# Schmeatic.net
KiCad netlist of a schematic drawn in Altium Designer
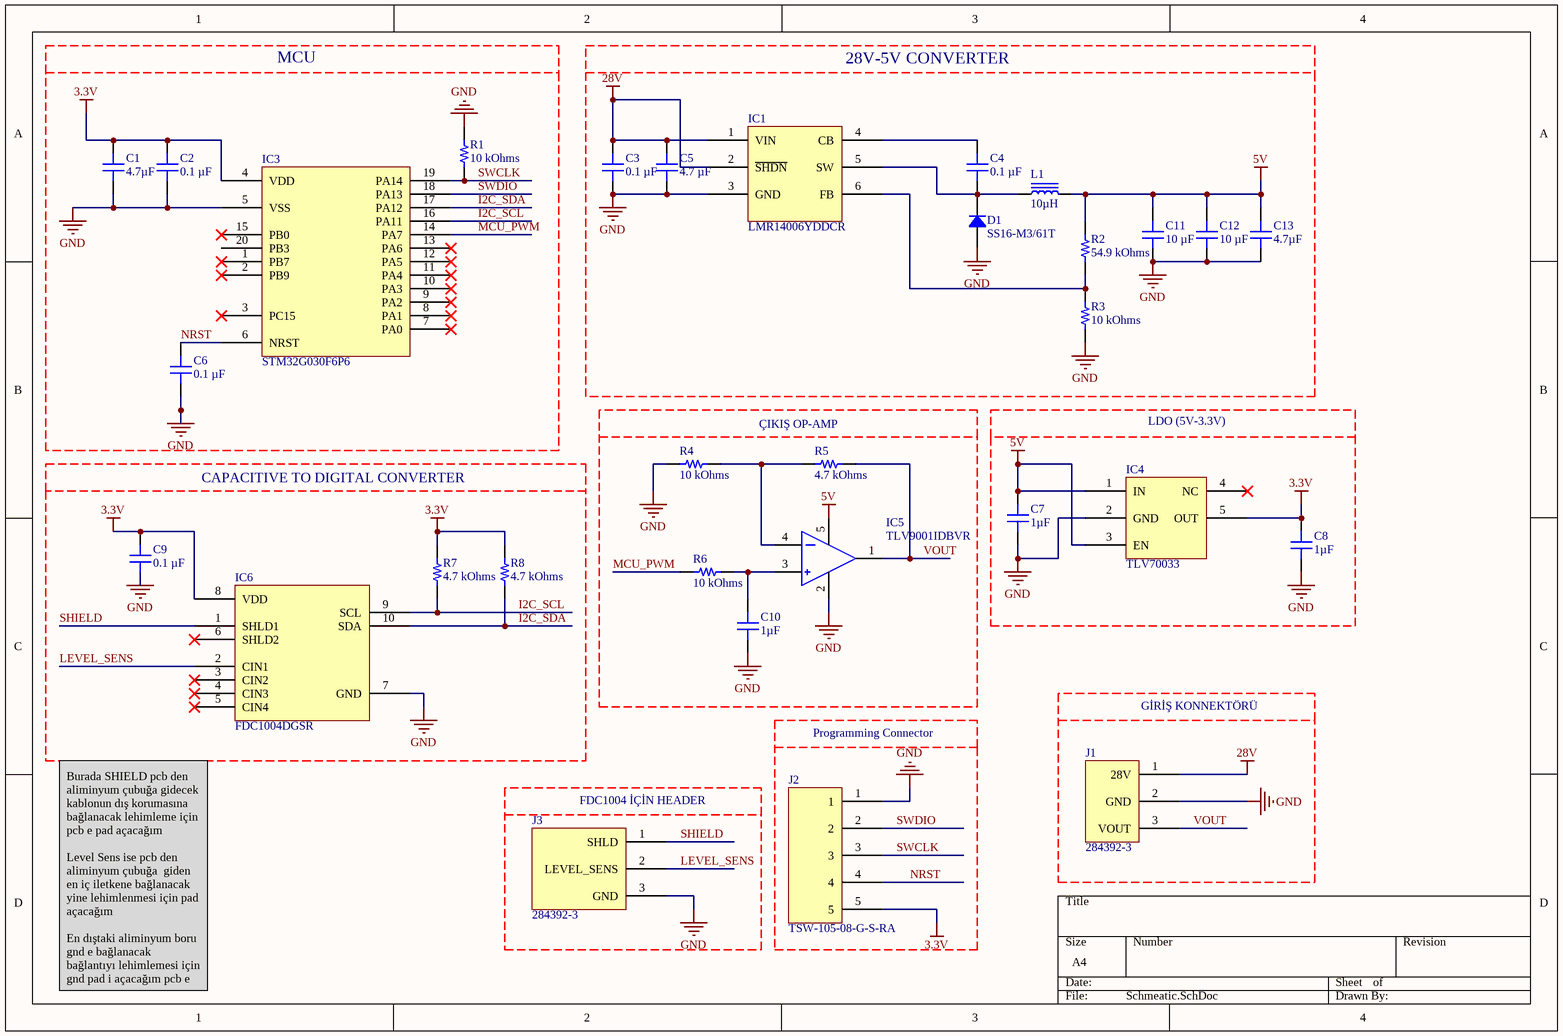
[diagram p0: Schmeatic.SchDoc]

(export (version "E")
  (design (tool "Eeschema 10.0.6"))
  (components
    (comp (ref "C1")
      (value "4.7µF")
      (footprint "CAP 0805_2012")
      (description "CAP CER 4.7UF 16V X7R 0805")
      (fields
        (field (name "PART NUMBER") "0805YC475MAT2A")
        (field (name "CAPACITANCE") "4.7µF")
        (field (name "MANUFACTURER") "AVX Corporation")
      )
      (libsource (lib "Celestial Altium Library - altium_library") (part "Capacitor"))
    )
    (comp (ref "C2")
      (value "0.1 µF")
      (footprint "CAP 0805_2012")
      (description "CAP CER 0.1UF 16V X7R 0805")
      (fields
        (field (name "PART NUMBER") "160R15W104KV4T")
        (field (name "CAPACITANCE") "0.1 µF")
        (field (name "MANUFACTURER") "Johanson Dielectrics Inc.")
      )
      (libsource (lib "Celestial Altium Library - altium_library") (part "Capacitor"))
    )
    (comp (ref "C3")
      (value "0.1 µF")
      (footprint "CAP 0805_2012")
      (description "CAP CER 0.1UF 50V X7R 0805")
      (fields
        (field (name "PART NUMBER") "885012207098")
        (field (name "CAPACITANCE") "0.1 µF")
        (field (name "MANUFACTURER") "Würth Elektronik")
      )
      (libsource (lib "Celestial Altium Library - altium_library") (part "Capacitor"))
    )
    (comp (ref "C4")
      (value "0.1 µF")
      (footprint "CAP 0805_2012")
      (description "CAP CER 0.1UF 25V X7R 0805")
      (fields
        (field (name "PART NUMBER") "0805Y0250104KXT")
        (field (name "CAPACITANCE") "0.1 µF")
        (field (name "MANUFACTURER") "Knowles Syfer")
      )
      (libsource (lib "Celestial Altium Library - altium_library") (part "Capacitor"))
    )
    (comp (ref "C5")
      (value "4.7 µF")
      (footprint "CAP 0805_2012")
      (description "CAP CER 4.7UF 50V X7R 0805")
      (fields
        (field (name "PART NUMBER") "CGA4J1X7R1H475K125AE")
        (field (name "CAPACITANCE") "4.7 µF")
        (field (name "MANUFACTURER") "TDK Corporation")
      )
      (libsource (lib "Celestial Altium Library - altium_library") (part "Capacitor"))
    )
    (comp (ref "C6")
      (value "0.1 µF")
      (footprint "CAP 0805_2012")
      (description "CAP CER 0.1UF 16V X7R 0805")
      (fields
        (field (name "PART NUMBER") "160R15W104KV4T")
        (field (name "CAPACITANCE") "0.1 µF")
        (field (name "MANUFACTURER") "Johanson Dielectrics Inc.")
      )
      (libsource (lib "Celestial Altium Library - altium_library") (part "Capacitor"))
    )
    (comp (ref "C7")
      (value "1µF")
      (footprint "CAP 0805_2012")
      (description "CAP CER 1UF 16V X7R 0805")
      (fields
        (field (name "PART NUMBER") "0805YC105KAT4A")
        (field (name "CAPACITANCE") "1µF")
        (field (name "MANUFACTURER") "AVX Corporation")
      )
      (libsource (lib "Celestial Altium Library - altium_library") (part "Capacitor"))
    )
    (comp (ref "C8")
      (value "1µF")
      (footprint "CAP 0805_2012")
      (description "CAP CER 1UF 16V X7R 0805")
      (fields
        (field (name "PART NUMBER") "0805YC105KAT4A")
        (field (name "CAPACITANCE") "1µF")
        (field (name "MANUFACTURER") "AVX Corporation")
      )
      (libsource (lib "Celestial Altium Library - altium_library") (part "Capacitor"))
    )
    (comp (ref "C9")
      (value "0.1 µF")
      (footprint "CAP 0805_2012")
      (description "CAP CER 0.1UF 16V X7R 0805")
      (fields
        (field (name "PART NUMBER") "160R15W104KV4T")
        (field (name "CAPACITANCE") "0.1 µF")
        (field (name "MANUFACTURER") "Johanson Dielectrics Inc.")
      )
      (libsource (lib "Celestial Altium Library - altium_library") (part "Capacitor"))
    )
    (comp (ref "C10")
      (value "1µF")
      (footprint "CAP 0805_2012")
      (description "CAP CER 1UF 16V X7R 0805")
      (fields
        (field (name "PART NUMBER") "0805YC105KAT4A")
        (field (name "CAPACITANCE") "1µF")
        (field (name "MANUFACTURER") "AVX Corporation")
      )
      (libsource (lib "Celestial Altium Library - altium_library") (part "Capacitor"))
    )
    (comp (ref "C11")
      (value "10 µF")
      (footprint "MURATA GRM21B 0805_2012")
      (description "CAP CER 10UF 25V X7R 0805")
      (fields
        (field (name "PART NUMBER") "GRM21BZ71E106KE15L")
        (field (name "CAPACITANCE") "10 µF")
        (field (name "MANUFACTURER") "Murata Electronics")
      )
      (libsource (lib "Celestial Altium Library - altium_library") (part "Capacitor"))
    )
    (comp (ref "C12")
      (value "10 µF")
      (footprint "MURATA GRM21B 0805_2012")
      (description "CAP CER 10UF 25V X7R 0805")
      (fields
        (field (name "PART NUMBER") "GRM21BZ71E106KE15L")
        (field (name "CAPACITANCE") "10 µF")
        (field (name "MANUFACTURER") "Murata Electronics")
      )
      (libsource (lib "Celestial Altium Library - altium_library") (part "Capacitor"))
    )
    (comp (ref "C13")
      (value "4.7µF")
      (footprint "CAP 0805_2012")
      (description "CAP CER 4.7UF 25V X7R 0805")
      (fields
        (field (name "PART NUMBER") "08053C475MAT2A")
        (field (name "CAPACITANCE") "4.7µF")
        (field (name "MANUFACTURER") "AVX Corporation")
      )
      (libsource (lib "Celestial Altium Library - altium_library") (part "Capacitor"))
    )
    (comp (ref "D1")
      (value "SS16-M3/61T")
      (footprint "DO214AC SMA")
      (description "DIODE SCHOTTKY 1A 60V DO-214AC")
      (fields (field (name "MANUFACTURER") "Vishay Semiconductor Diodes Division"))
      (libsource (lib "Celestial Altium Library - altium_library") (part "Diode"))
    )
    (comp (ref "IC1")
      (value "LMR14006YDDCR")
      (footprint "PcbLib1:TSOT-23-6")
      (description "Buck Switching Regulator IC Positive Adjustable 0.765V 1 Output 600mA SOT-23-6 Thin, TSOT-23-6")
      (libsource (lib "Schlib1") (part "LMR14006YDDCR"))
    )
    (comp (ref "IC3")
      (value "STM32G030F6P6")
      (footprint "TSSOP20")
      (description "ARM® Cortex®-M0+ STM32G0 Microcontroller IC 32-Bit 64MHz 32KB (32K x 8) FLASH 20-TSSOP")
      (libsource (lib "Schlib1") (part "STM32G030F6P6"))
    )
    (comp (ref "IC4")
      (value "TLV70033")
      (footprint "SOT23-5")
      (description "Linear Voltage Regulator IC Positive Fixed 1 Output 200mA SC-70-5")
      (libsource (lib "Schlib1") (part "TLV70033"))
    )
    (comp (ref "IC5")
      (value "TLV9001IDBVR")
      (footprint "PcbLib1:SOT23-5")
      (description "CMOS Amplifier 1 Circuit Rail-to-Rail SOT-23-5")
      (libsource (lib "Schlib1") (part "TLV9001IDBVR"))
    )
    (comp (ref "IC6")
      (value "FDC1004DGSR")
      (footprint "10-VSSOP (DGS)")
      (description "Capacitive Touch Proximity Only 10-VSSOP")
      (libsource (lib "Schlib1") (part "FDC1004DGSR"))
    )
    (comp (ref "J1")
      (value "284392-3")
      (footprint "PcbLib1:284392-3")
      (description "3 Position Wire to Board Terminal Block Horizontal with Board 0.150\" (3.81mm) Through Hole")
      (libsource (lib "Schlib1") (part "284392-3"))
    )
    (comp (ref "J2")
      (value "TSW-105-08-G-S-RA")
      (footprint "TSW-105-08-G-S-RA")
      (description "Connector Header Through Hole, Right Angle 5 position 0.100\" (2.54mm)")
      (libsource (lib "Schlib1") (part "TSW-105-08-G-S-RA"))
    )
    (comp (ref "J3")
      (value "284392-3")
      (footprint "284392-3")
      (description "3 Position Wire to Board Terminal Block Horizontal with Board 0.150\" (3.81mm) Through Hole")
      (libsource (lib "Schlib1") (part "284392-3 (FDC1004 İÇİN)"))
    )
    (comp (ref "L1")
      (value "10µH")
      (footprint "TDK SLF7032")
      (description "FIXED IND 10UH 1.4A 63.6 MOHM")
      (fields
        (field (name "PART NUMBER") "SLF7032T-100M1R4-2PF")
        (field (name "MANUFACTURER") "TDK Corporation")
      )
      (libsource (lib "Celestial Altium Library - altium_library") (part "Inductor"))
    )
    (comp (ref "R1")
      (value "10 kOhms")
      (footprint "YAGEO RES 0805_2012")
      (description "RES 10K OHM 1% 1/8W 0805")
      (fields (field (name "PART NUMBER") "RV0805FR-0710KL") (field (name "MANUFACTURER") "Yageo"))
      (libsource (lib "Celestial Altium Library - altium_library") (part "Resistor"))
    )
    (comp (ref "R2")
      (value "54.9 kOhms")
      (footprint "RES 0805_2012")
      (description "RES SMD 54.9K OHM 1% 1/8W 0805")
      (fields (field (name "PART NUMBER") "CRCW080554K9FKEA") (field (name "MANUFACTURER") "Vishay Dale"))
      (libsource (lib "Celestial Altium Library - altium_library") (part "Resistor"))
    )
    (comp (ref "R3")
      (value "10 kOhms")
      (footprint "YAGEO RES 0805_2012")
      (description "RES SMD 10K OHM 1% 1/8W 0805")
      (fields (field (name "PART NUMBER") "RT0805FRE0710KL") (field (name "MANUFACTURER") "Yageo"))
      (libsource (lib "Celestial Altium Library - altium_library") (part "Resistor"))
    )
    (comp (ref "R4")
      (value "10 kOhms")
      (footprint "RES 0805_2012")
      (description "RES SMD 10K OHM 1% 1/8W 0805")
      (fields (field (name "PART NUMBER") "CRCW080510K0FKEA") (field (name "MANUFACTURER") "Vishay Dale"))
      (libsource (lib "Celestial Altium Library - altium_library") (part "Resistor"))
    )
    (comp (ref "R5")
      (value "4.7 kOhms")
      (footprint "YAGEO RES 0805_2012")
      (description "RES 4.7K OHM 1% 1/8W 0805")
      (fields (field (name "PART NUMBER") "RC0805FR-074K7P") (field (name "MANUFACTURER") "Yageo"))
      (libsource (lib "Celestial Altium Library - altium_library") (part "Resistor"))
    )
    (comp (ref "R6")
      (value "10 kOhms")
      (footprint "RES 0805_2012")
      (description "RES SMD 10K OHM 1% 1/8W 0805")
      (fields (field (name "PART NUMBER") "CRCW080510K0FKEA") (field (name "MANUFACTURER") "Vishay Dale"))
      (libsource (lib "Celestial Altium Library - altium_library") (part "Resistor"))
    )
    (comp (ref "R7")
      (value "4.7 kOhms")
      (footprint "YAGEO RES 0805_2012")
      (description "RES 4.7K OHM 1% 1/8W 0805")
      (fields (field (name "PART NUMBER") "RC0805FR-074K7P") (field (name "MANUFACTURER") "Yageo"))
      (libsource (lib "Celestial Altium Library - altium_library") (part "Resistor"))
    )
    (comp (ref "R8")
      (value "4.7 kOhms")
      (footprint "YAGEO RES 0805_2012")
      (description "RES 4.7K OHM 1% 1/8W 0805")
      (fields (field (name "PART NUMBER") "RC0805FR-074K7P") (field (name "MANUFACTURER") "Yageo"))
      (libsource (lib "Celestial Altium Library - altium_library") (part "Resistor"))
    )
  )
  (nets
    (net (code "1") (name "/I2C_SCL") (class "Default")
      (node (ref "IC3") (pin "16") (pinfunction "PA11_16") (pintype "passive"))
      (node (ref "IC6") (pin "9") (pinfunction "SCL_9") (pintype "passive"))
      (node (ref "R7") (pin "1") (pinfunction "1_1") (pintype "passive"))
    )
    (net (code "2") (name "/I2C_SDA") (class "Default")
      (node (ref "IC3") (pin "17") (pinfunction "PA12_17") (pintype "passive"))
      (node (ref "IC6") (pin "10") (pinfunction "SDA_10") (pintype "passive"))
      (node (ref "R8") (pin "1") (pinfunction "1_1") (pintype "passive"))
    )
    (net (code "3") (name "/LEVEL_SENS") (class "Default")
      (node (ref "IC6") (pin "2") (pinfunction "CIN1_2") (pintype "passive"))
      (node (ref "J3") (pin "2") (pinfunction "LEVEL_SENS_2") (pintype "passive"))
    )
    (net (code "4") (name "/MCU_PWM") (class "Default")
      (node (ref "IC3") (pin "14") (pinfunction "PA7_14") (pintype "passive"))
      (node (ref "R6") (pin "1") (pinfunction "1_1") (pintype "passive"))
    )
    (net (code "5") (name "/NRST") (class "Default")
      (node (ref "C6") (pin "2") (pinfunction "2_2") (pintype "passive"))
      (node (ref "IC3") (pin "6") (pinfunction "NRST_6") (pintype "passive"))
      (node (ref "J2") (pin "4") (pinfunction "4_4") (pintype "passive"))
    )
    (net (code "6") (name "/SHIELD") (class "Default")
      (node (ref "IC6") (pin "1") (pinfunction "SHLD1_1") (pintype "passive"))
      (node (ref "J3") (pin "1") (pinfunction "SHLD_1") (pintype "passive"))
    )
    (net (code "7") (name "/SWCLK") (class "Default")
      (node (ref "IC3") (pin "19") (pinfunction "PA14_19") (pintype "passive"))
      (node (ref "J2") (pin "3") (pinfunction "3_3") (pintype "passive"))
      (node (ref "R1") (pin "1") (pinfunction "1_1") (pintype "passive"))
    )
    (net (code "8") (name "/SWDIO") (class "Default")
      (node (ref "IC3") (pin "18") (pinfunction "PA13_18") (pintype "passive"))
      (node (ref "J2") (pin "2") (pinfunction "2_2") (pintype "passive"))
    )
    (net (code "9") (name "/VOUT") (class "Default")
      (node (ref "IC5") (pin "1") (pinfunction "1_1") (pintype "passive"))
      (node (ref "J1") (pin "3") (pinfunction "VOUT_3") (pintype "passive"))
      (node (ref "R5") (pin "2") (pinfunction "2_2") (pintype "passive"))
    )
    (net (code "10") (name "3.3V") (class "Default")
      (node (ref "C1") (pin "2") (pinfunction "2_2") (pintype "passive"))
      (node (ref "C2") (pin "2") (pinfunction "2_2") (pintype "passive"))
      (node (ref "C8") (pin "1") (pinfunction "1_1") (pintype "passive"))
      (node (ref "C9") (pin "2") (pinfunction "2_2") (pintype "passive"))
      (node (ref "IC3") (pin "4") (pinfunction "VDD_4") (pintype "passive"))
      (node (ref "IC4") (pin "5") (pinfunction "OUT_5") (pintype "passive"))
      (node (ref "IC6") (pin "8") (pinfunction "VDD_8") (pintype "passive"))
      (node (ref "J2") (pin "5") (pinfunction "5_5") (pintype "passive"))
      (node (ref "R7") (pin "2") (pinfunction "2_2") (pintype "passive"))
      (node (ref "R8") (pin "2") (pinfunction "2_2") (pintype "passive"))
    )
    (net (code "11") (name "5V") (class "Default")
      (node (ref "C11") (pin "2") (pinfunction "2_2") (pintype "passive"))
      (node (ref "C12") (pin "2") (pinfunction "2_2") (pintype "passive"))
      (node (ref "C13") (pin "2") (pinfunction "2_2") (pintype "passive"))
      (node (ref "C7") (pin "1") (pinfunction "1_1") (pintype "passive"))
      (node (ref "IC4") (pin "1") (pinfunction "IN_1") (pintype "passive"))
      (node (ref "IC4") (pin "3") (pinfunction "EN_3") (pintype "passive"))
      (node (ref "IC5") (pin "5") (pinfunction "5_5") (pintype "passive"))
      (node (ref "L1") (pin "2") (pinfunction "2_2") (pintype "passive"))
      (node (ref "R2") (pin "2") (pinfunction "2_2") (pintype "passive"))
    )
    (net (code "12") (name "28V") (class "Default")
      (node (ref "C3") (pin "2") (pinfunction "2_2") (pintype "passive"))
      (node (ref "C5") (pin "2") (pinfunction "2_2") (pintype "passive"))
      (node (ref "IC1") (pin "1") (pinfunction "VIN_1") (pintype "passive"))
      (node (ref "IC1") (pin "2") (pinfunction "~{SHDN}_2") (pintype "passive"))
      (node (ref "J1") (pin "1") (pinfunction "28V_1") (pintype "passive"))
    )
    (net (code "13") (name "GND") (class "Default")
      (node (ref "C1") (pin "1") (pinfunction "1_1") (pintype "passive"))
      (node (ref "C10") (pin "2") (pinfunction "2_2") (pintype "passive"))
      (node (ref "C11") (pin "1") (pinfunction "1_1") (pintype "passive"))
      (node (ref "C12") (pin "1") (pinfunction "1_1") (pintype "passive"))
      (node (ref "C13") (pin "1") (pinfunction "1_1") (pintype "passive"))
      (node (ref "C2") (pin "1") (pinfunction "1_1") (pintype "passive"))
      (node (ref "C3") (pin "1") (pinfunction "1_1") (pintype "passive"))
      (node (ref "C5") (pin "1") (pinfunction "1_1") (pintype "passive"))
      (node (ref "C6") (pin "1") (pinfunction "1_1") (pintype "passive"))
      (node (ref "C7") (pin "2") (pinfunction "2_2") (pintype "passive"))
      (node (ref "C8") (pin "2") (pinfunction "2_2") (pintype "passive"))
      (node (ref "C9") (pin "1") (pinfunction "1_1") (pintype "passive"))
      (node (ref "D1") (pin "1") (pinfunction "1_1") (pintype "passive"))
      (node (ref "IC1") (pin "3") (pinfunction "GND_3") (pintype "passive"))
      (node (ref "IC3") (pin "5") (pinfunction "VSS_5") (pintype "passive"))
      (node (ref "IC4") (pin "2") (pinfunction "GND_2") (pintype "passive"))
      (node (ref "IC5") (pin "2") (pinfunction "2_2") (pintype "passive"))
      (node (ref "IC6") (pin "7") (pinfunction "GND_7") (pintype "passive"))
      (node (ref "J1") (pin "2") (pinfunction "GND_2") (pintype "passive"))
      (node (ref "J2") (pin "1") (pinfunction "1_1") (pintype "passive"))
      (node (ref "J3") (pin "3") (pinfunction "GND_3") (pintype "passive"))
      (node (ref "R1") (pin "2") (pinfunction "2_2") (pintype "passive"))
      (node (ref "R3") (pin "1") (pinfunction "1_1") (pintype "passive"))
      (node (ref "R4") (pin "1") (pinfunction "1_1") (pintype "passive"))
    )
    (net (code "14") (name "Net-(C10-Pad1)") (class "Default")
      (node (ref "C10") (pin "1") (pinfunction "1_1") (pintype "passive"))
      (node (ref "IC5") (pin "3") (pinfunction "3_3") (pintype "passive"))
      (node (ref "R6") (pin "2") (pinfunction "2_2") (pintype "passive"))
    )
    (net (code "15") (name "Net-(IC1-CB)") (class "Default")
      (node (ref "C4") (pin "2") (pinfunction "2_2") (pintype "passive"))
      (node (ref "IC1") (pin "4") (pinfunction "CB_4") (pintype "passive"))
    )
    (net (code "16") (name "Net-(IC1-FB)") (class "Default")
      (node (ref "IC1") (pin "6") (pinfunction "FB_6") (pintype "passive"))
      (node (ref "R2") (pin "1") (pinfunction "1_1") (pintype "passive"))
      (node (ref "R3") (pin "2") (pinfunction "2_2") (pintype "passive"))
    )
    (net (code "17") (name "Net-(IC1-SW)") (class "Default")
      (node (ref "C4") (pin "1") (pinfunction "1_1") (pintype "passive"))
      (node (ref "D1") (pin "2") (pinfunction "2_2") (pintype "passive"))
      (node (ref "IC1") (pin "5") (pinfunction "SW_5") (pintype "passive"))
      (node (ref "L1") (pin "1") (pinfunction "1_1") (pintype "passive"))
    )
    (net (code "18") (name "Net-(IC5-Pad4)") (class "Default")
      (node (ref "IC5") (pin "4") (pinfunction "4_4") (pintype "passive"))
      (node (ref "R4") (pin "2") (pinfunction "2_2") (pintype "passive"))
      (node (ref "R5") (pin "1") (pinfunction "1_1") (pintype "passive"))
    )
    (net (code "19") (name "unconnected-(IC3-PA0-Pad7)") (class "Default")
      (node (ref "IC3") (pin "7") (pinfunction "PA0_7") (pintype "passive+no_connect"))
    )
    (net (code "20") (name "unconnected-(IC3-PA1-Pad8)") (class "Default")
      (node (ref "IC3") (pin "8") (pinfunction "PA1_8") (pintype "passive+no_connect"))
    )
    (net (code "21") (name "unconnected-(IC3-PA2-Pad9)") (class "Default")
      (node (ref "IC3") (pin "9") (pinfunction "PA2_9") (pintype "passive+no_connect"))
    )
    (net (code "22") (name "unconnected-(IC3-PA3-Pad10)") (class "Default")
      (node (ref "IC3") (pin "10") (pinfunction "PA3_10") (pintype "passive+no_connect"))
    )
    (net (code "23") (name "unconnected-(IC3-PA4-Pad11)") (class "Default")
      (node (ref "IC3") (pin "11") (pinfunction "PA4_11") (pintype "passive+no_connect"))
    )
    (net (code "24") (name "unconnected-(IC3-PA5-Pad12)") (class "Default")
      (node (ref "IC3") (pin "12") (pinfunction "PA5_12") (pintype "passive+no_connect"))
    )
    (net (code "25") (name "unconnected-(IC3-PA6-Pad13)") (class "Default")
      (node (ref "IC3") (pin "13") (pinfunction "PA6_13") (pintype "passive+no_connect"))
    )
    (net (code "26") (name "unconnected-(IC3-PB0-Pad15)") (class "Default")
      (node (ref "IC3") (pin "15") (pinfunction "PB0_15") (pintype "passive+no_connect"))
    )
    (net (code "27") (name "unconnected-(IC3-PB3-Pad20)") (class "Default")
      (node (ref "IC3") (pin "20") (pinfunction "PB3_20") (pintype "passive"))
    )
    (net (code "28") (name "unconnected-(IC3-PB7-Pad1)") (class "Default")
      (node (ref "IC3") (pin "1") (pinfunction "PB7_1") (pintype "passive+no_connect"))
    )
    (net (code "29") (name "unconnected-(IC3-PB9-Pad2)") (class "Default")
      (node (ref "IC3") (pin "2") (pinfunction "PB9_2") (pintype "passive+no_connect"))
    )
    (net (code "30") (name "unconnected-(IC3-PC15-Pad3)") (class "Default")
      (node (ref "IC3") (pin "3") (pinfunction "PC15_3") (pintype "passive+no_connect"))
    )
    (net (code "31") (name "unconnected-(IC4-NC-Pad4)") (class "Default")
      (node (ref "IC4") (pin "4") (pinfunction "NC_4") (pintype "passive+no_connect"))
    )
    (net (code "32") (name "unconnected-(IC6-CIN2-Pad3)") (class "Default")
      (node (ref "IC6") (pin "3") (pinfunction "CIN2_3") (pintype "passive+no_connect"))
    )
    (net (code "33") (name "unconnected-(IC6-CIN3-Pad4)") (class "Default")
      (node (ref "IC6") (pin "4") (pinfunction "CIN3_4") (pintype "passive+no_connect"))
    )
    (net (code "34") (name "unconnected-(IC6-CIN4-Pad5)") (class "Default")
      (node (ref "IC6") (pin "5") (pinfunction "CIN4_5") (pintype "passive+no_connect"))
    )
    (net (code "35") (name "unconnected-(IC6-SHLD2-Pad6)") (class "Default")
      (node (ref "IC6") (pin "6") (pinfunction "SHLD2_6") (pintype "passive+no_connect"))
    )
  )
)
